# RPL_IMU.net
KiCad netlist of a schematic drawn in Altium Designer
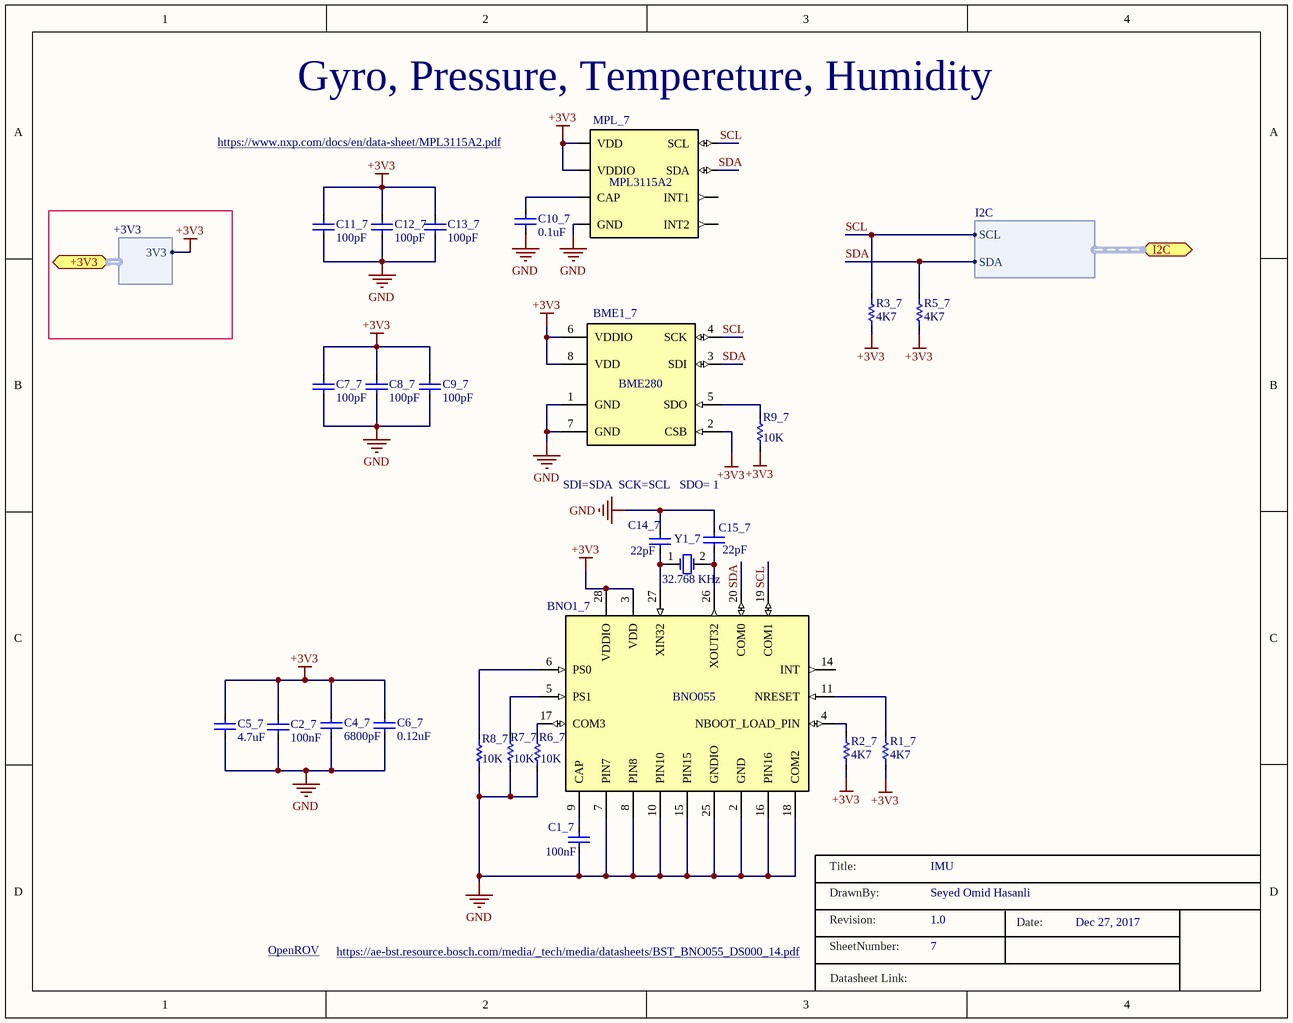
[diagram p0: RPL_IMU.SchDoc]

(export (version "E")
  (design (tool "Eeschema 10.0.6"))
  (components
    (comp (ref "BME1_7")
      (value "BME280")
      (footprint "BME280")
      (description "Integrated pressure, humidity and temperature sensor; 8-pin 2.5x2.5x0.93mm LGA")
      (fields (field (name "MF") "Bosch"))
      (libsource (lib "Generic_Library") (part "BME280"))
    )
    (comp (ref "BNO1_7")
      (value "BNO055")
      (footprint "LGA28R50P4X10_380X520X100")
      (description "BNO055 9-axis Absolute Orientation Sensor ( SiP ) w/Sensors and Sensor Fusion")
      (fields (field (name "MF") "Bosch"))
      (libsource (lib "Generic_Library") (part "BNO055"))
    )
    (comp (ref "C1_7")
      (value "100nF")
      (footprint "C0805C475K9RACAUTO")
      (fields (field (name "Comment") "Cap"))
      (libsource (lib "Generic_Library") (part "Cap"))
    )
    (comp (ref "C2_7")
      (value "100nF")
      (footprint "C0805C475K9RACAUTO")
      (fields (field (name "Comment") "Cap"))
      (libsource (lib "Generic_Library") (part "Cap"))
    )
    (comp (ref "C4_7")
      (value "6800pF")
      (footprint "C0805C475K9RACAUTO")
      (fields (field (name "Comment") "Cap"))
      (libsource (lib "Generic_Library") (part "Cap"))
    )
    (comp (ref "C5_7")
      (value "4.7uF")
      (footprint "C0805C475K9RACAUTO")
      (fields (field (name "Comment") "Cap"))
      (libsource (lib "Generic_Library") (part "Cap"))
    )
    (comp (ref "C6_7")
      (value "0.12uF")
      (footprint "C0805C475K9RACAUTO")
      (fields (field (name "Comment") "Cap"))
      (libsource (lib "Generic_Library") (part "Cap"))
    )
    (comp (ref "C7_7")
      (value "100pF")
      (footprint "C0805C475K9RACAUTO")
      (fields (field (name "Comment") "Cap"))
      (libsource (lib "Generic_Library") (part "Cap"))
    )
    (comp (ref "C8_7")
      (value "100pF")
      (footprint "C0805C475K9RACAUTO")
      (fields (field (name "Comment") "Cap"))
      (libsource (lib "Generic_Library") (part "Cap"))
    )
    (comp (ref "C9_7")
      (value "100pF")
      (footprint "C0805C475K9RACAUTO")
      (fields (field (name "Comment") "Cap"))
      (libsource (lib "Generic_Library") (part "Cap"))
    )
    (comp (ref "C10_7")
      (value "0.1uF")
      (footprint "C0805C475K9RACAUTO")
      (fields (field (name "Comment") "Cap"))
      (libsource (lib "Generic_Library") (part "Cap"))
    )
    (comp (ref "C11_7")
      (value "100pF")
      (footprint "C0805C475K9RACAUTO")
      (fields (field (name "Comment") "Cap"))
      (libsource (lib "Generic_Library") (part "Cap"))
    )
    (comp (ref "C12_7")
      (value "100pF")
      (footprint "C0805C475K9RACAUTO")
      (fields (field (name "Comment") "Cap"))
      (libsource (lib "Generic_Library") (part "Cap"))
    )
    (comp (ref "C13_7")
      (value "100pF")
      (footprint "C0805C475K9RACAUTO")
      (fields (field (name "Comment") "Cap"))
      (libsource (lib "Generic_Library") (part "Cap"))
    )
    (comp (ref "C14_7")
      (value "22pF")
      (footprint "C0805C475K9RACAUTO")
      (fields (field (name "Comment") "Cap"))
      (libsource (lib "Generic_Library") (part "Cap"))
    )
    (comp (ref "C15_7")
      (value "22pF")
      (footprint "C0805C475K9RACAUTO")
      (fields (field (name "Comment") "Cap"))
      (libsource (lib "Generic_Library") (part "Cap"))
    )
    (comp (ref "MPL_7")
      (value "MPL3115A2")
      (footprint "LGA8")
      (description "Pressure Sensor, 50-110kpa, Lga-8")
      (fields (field (name "MF") "NXP Semiconductors"))
      (libsource (lib "Generic_Library") (part "MPL3115A2"))
    )
    (comp (ref "R1_7")
      (value "4K7")
      (footprint "SMD Resistors:RES 0805")
      (fields (field (name "Comment") "Res"))
      (libsource (lib "Generic_Library") (part "Res"))
    )
    (comp (ref "R2_7")
      (value "4K7")
      (footprint "SMD Resistors:RES 0805")
      (fields (field (name "Comment") "Res"))
      (libsource (lib "Generic_Library") (part "Res"))
    )
    (comp (ref "R3_7")
      (value "4K7")
      (footprint "SMD Resistors:RES 0805")
      (fields (field (name "Comment") "Res"))
      (libsource (lib "Generic_Library") (part "Res"))
    )
    (comp (ref "R5_7")
      (value "4K7")
      (footprint "SMD Resistors:RES 0805")
      (fields (field (name "Comment") "Res"))
      (libsource (lib "Generic_Library") (part "Res"))
    )
    (comp (ref "R6_7")
      (value "10K")
      (footprint "SMD Resistors:RES 0805")
      (fields (field (name "Comment") "Res"))
      (libsource (lib "Generic_Library") (part "Res"))
    )
    (comp (ref "R7_7")
      (value "10K")
      (footprint "SMD Resistors:RES 0805")
      (fields (field (name "Comment") "Res"))
      (libsource (lib "Generic_Library") (part "Res"))
    )
    (comp (ref "R8_7")
      (value "10K")
      (footprint "SMD Resistors:RES 0805")
      (fields (field (name "Comment") "Res"))
      (libsource (lib "Generic_Library") (part "Res"))
    )
    (comp (ref "R9_7")
      (value "10K")
      (footprint "SMD Resistors:RES 0805")
      (fields (field (name "Comment") "Res"))
      (libsource (lib "Generic_Library") (part "Res"))
    )
    (comp (ref "Y1_7")
      (value "32.768 KHz")
      (footprint "FC-135R 32.7680KA-A3")
      (fields (field (name "Comment") "16MHz"))
      (libsource (lib "Generic_Library") (part "XTAL"))
    )
  )
  (nets
    (net (code "2") (name "+3V3") (class "Default")
      (node (ref "BME1_7") (pin "2") (pinfunction "CSB_2") (pintype "input"))
      (node (ref "BME1_7") (pin "6") (pinfunction "VDDIO_6") (pintype "power_in"))
      (node (ref "BME1_7") (pin "8") (pinfunction "VDD_8") (pintype "power_in"))
      (node (ref "BNO1_7") (pin "28") (pinfunction "VDDIO_28") (pintype "power_in"))
      (node (ref "BNO1_7") (pin "3") (pinfunction "VDD_3") (pintype "power_in"))
      (node (ref "C11_7") (pin "2") (pinfunction "2_2") (pintype "passive"))
      (node (ref "C12_7") (pin "2") (pinfunction "2_2") (pintype "passive"))
      (node (ref "C13_7") (pin "2") (pinfunction "2_2") (pintype "passive"))
      (node (ref "C2_7") (pin "2") (pinfunction "2_2") (pintype "passive"))
      (node (ref "C4_7") (pin "2") (pinfunction "2_2") (pintype "passive"))
      (node (ref "C5_7") (pin "2") (pinfunction "2_2") (pintype "passive"))
      (node (ref "C6_7") (pin "2") (pinfunction "2_2") (pintype "passive"))
      (node (ref "C7_7") (pin "2") (pinfunction "2_2") (pintype "passive"))
      (node (ref "C8_7") (pin "2") (pinfunction "2_2") (pintype "passive"))
      (node (ref "C9_7") (pin "2") (pinfunction "2_2") (pintype "passive"))
      (node (ref "MPL_7") (pin "1") (pinfunction "VDD_1") (pintype "power_in"))
      (node (ref "MPL_7") (pin "4") (pinfunction "VDDIO_4") (pintype "power_in"))
      (node (ref "R1_7") (pin "1") (pinfunction "1_1") (pintype "passive"))
      (node (ref "R2_7") (pin "1") (pinfunction "1_1") (pintype "passive"))
      (node (ref "R3_7") (pin "1") (pinfunction "1_1") (pintype "passive"))
      (node (ref "R5_7") (pin "1") (pinfunction "1_1") (pintype "passive"))
      (node (ref "R9_7") (pin "1") (pinfunction "1_1") (pintype "passive"))
    )
    (net (code "3") (name "/SCL") (class "Default")
      (node (ref "BME1_7") (pin "4") (pinfunction "SCK_4") (pintype "bidirectional"))
      (node (ref "BNO1_7") (pin "19") (pinfunction "COM1_19") (pintype "bidirectional"))
      (node (ref "MPL_7") (pin "8") (pinfunction "SCL_8") (pintype "bidirectional"))
      (node (ref "R3_7") (pin "2") (pinfunction "2_2") (pintype "passive"))
    )
    (net (code "4") (name "/SDA") (class "Default")
      (node (ref "BME1_7") (pin "3") (pinfunction "SDI_3") (pintype "bidirectional"))
      (node (ref "BNO1_7") (pin "20") (pinfunction "COM0_20") (pintype "bidirectional"))
      (node (ref "MPL_7") (pin "7") (pinfunction "SDA_7") (pintype "bidirectional"))
      (node (ref "R5_7") (pin "2") (pinfunction "2_2") (pintype "passive"))
    )
    (net (code "7") (name "GND") (class "Default")
      (node (ref "BME1_7") (pin "1") (pinfunction "GND_1") (pintype "power_in"))
      (node (ref "BME1_7") (pin "7") (pinfunction "GND_7") (pintype "power_in"))
      (node (ref "BNO1_7") (pin "10") (pinfunction "PIN10_10") (pintype "power_in"))
      (node (ref "BNO1_7") (pin "15") (pinfunction "PIN15_15") (pintype "power_in"))
      (node (ref "BNO1_7") (pin "16") (pinfunction "PIN16_16") (pintype "power_in"))
      (node (ref "BNO1_7") (pin "18") (pinfunction "COM2_18") (pintype "passive"))
      (node (ref "BNO1_7") (pin "2") (pinfunction "GND_2") (pintype "power_in"))
      (node (ref "BNO1_7") (pin "25") (pinfunction "GNDIO_25") (pintype "power_in"))
      (node (ref "BNO1_7") (pin "7") (pinfunction "PIN7_7") (pintype "passive"))
      (node (ref "BNO1_7") (pin "8") (pinfunction "PIN8_8") (pintype "passive"))
      (node (ref "C10_7") (pin "1") (pinfunction "1_1") (pintype "passive"))
      (node (ref "C11_7") (pin "1") (pinfunction "1_1") (pintype "passive"))
      (node (ref "C12_7") (pin "1") (pinfunction "1_1") (pintype "passive"))
      (node (ref "C13_7") (pin "1") (pinfunction "1_1") (pintype "passive"))
      (node (ref "C14_7") (pin "1") (pinfunction "1_1") (pintype "passive"))
      (node (ref "C15_7") (pin "1") (pinfunction "1_1") (pintype "passive"))
      (node (ref "C1_7") (pin "1") (pinfunction "1_1") (pintype "passive"))
      (node (ref "C2_7") (pin "1") (pinfunction "1_1") (pintype "passive"))
      (node (ref "C4_7") (pin "1") (pinfunction "1_1") (pintype "passive"))
      (node (ref "C5_7") (pin "1") (pinfunction "1_1") (pintype "passive"))
      (node (ref "C6_7") (pin "1") (pinfunction "1_1") (pintype "passive"))
      (node (ref "C7_7") (pin "1") (pinfunction "1_1") (pintype "passive"))
      (node (ref "C8_7") (pin "1") (pinfunction "1_1") (pintype "passive"))
      (node (ref "C9_7") (pin "1") (pinfunction "1_1") (pintype "passive"))
      (node (ref "MPL_7") (pin "3") (pinfunction "GND_3") (pintype "power_in"))
      (node (ref "R6_7") (pin "1") (pinfunction "1_1") (pintype "passive"))
      (node (ref "R7_7") (pin "1") (pinfunction "1_1") (pintype "passive"))
      (node (ref "R8_7") (pin "1") (pinfunction "1_1") (pintype "passive"))
    )
    (net (code "8") (name "Net-(BME1_7-SDO)") (class "Default")
      (node (ref "BME1_7") (pin "5") (pinfunction "SDO_5") (pintype "input"))
      (node (ref "R9_7") (pin "2") (pinfunction "2_2") (pintype "passive"))
    )
    (net (code "9") (name "Net-(BNO1_7-CAP)") (class "Default")
      (node (ref "BNO1_7") (pin "9") (pinfunction "CAP_9") (pintype "passive"))
      (node (ref "C1_7") (pin "2") (pinfunction "2_2") (pintype "passive"))
    )
    (net (code "10") (name "Net-(BNO1_7-COM3)") (class "Default")
      (node (ref "BNO1_7") (pin "17") (pinfunction "COM3_17") (pintype "bidirectional"))
      (node (ref "R6_7") (pin "2") (pinfunction "2_2") (pintype "passive"))
    )
    (net (code "11") (name "Net-(BNO1_7-NBOOT_LOAD_PIN)") (class "Default")
      (node (ref "BNO1_7") (pin "4") (pinfunction "NBOOT_LOAD_PIN_4") (pintype "bidirectional"))
      (node (ref "R2_7") (pin "2") (pinfunction "2_2") (pintype "passive"))
    )
    (net (code "12") (name "Net-(BNO1_7-NRESET)") (class "Default")
      (node (ref "BNO1_7") (pin "11") (pinfunction "NRESET_11") (pintype "input"))
      (node (ref "R1_7") (pin "2") (pinfunction "2_2") (pintype "passive"))
    )
    (net (code "13") (name "Net-(BNO1_7-PS0)") (class "Default")
      (node (ref "BNO1_7") (pin "6") (pinfunction "PS0_6") (pintype "input"))
      (node (ref "R8_7") (pin "2") (pinfunction "2_2") (pintype "passive"))
    )
    (net (code "14") (name "Net-(BNO1_7-PS1)") (class "Default")
      (node (ref "BNO1_7") (pin "5") (pinfunction "PS1_5") (pintype "input"))
      (node (ref "R7_7") (pin "2") (pinfunction "2_2") (pintype "passive"))
    )
    (net (code "15") (name "Net-(BNO1_7-XIN32)") (class "Default")
      (node (ref "BNO1_7") (pin "27") (pinfunction "XIN32_27") (pintype "input"))
      (node (ref "C14_7") (pin "2") (pinfunction "2_2") (pintype "passive"))
      (node (ref "Y1_7") (pin "1") (pinfunction "OSC1_1") (pintype "passive"))
    )
    (net (code "16") (name "Net-(BNO1_7-XOUT32)") (class "Default")
      (node (ref "BNO1_7") (pin "26") (pinfunction "XOUT32_26") (pintype "output"))
      (node (ref "C15_7") (pin "2") (pinfunction "2_2") (pintype "passive"))
      (node (ref "Y1_7") (pin "2") (pinfunction "OSC2_2") (pintype "passive"))
    )
    (net (code "17") (name "Net-(MPL_7-CAP)") (class "Default")
      (node (ref "C10_7") (pin "2") (pinfunction "2_2") (pintype "passive"))
      (node (ref "MPL_7") (pin "2") (pinfunction "CAP_2") (pintype "power_in"))
    )
    (net (code "18") (name "unconnected-(BNO1_7-INT-Pad14)") (class "Default")
      (node (ref "BNO1_7") (pin "14") (pinfunction "INT_14") (pintype "output"))
    )
    (net (code "19") (name "unconnected-(MPL_7-INT1-Pad6)") (class "Default")
      (node (ref "MPL_7") (pin "6") (pinfunction "INT1_6") (pintype "output"))
    )
    (net (code "20") (name "unconnected-(MPL_7-INT2-Pad5)") (class "Default")
      (node (ref "MPL_7") (pin "5") (pinfunction "INT2_5") (pintype "output"))
    )
  )
)
